# Connecteurs.net
KiCad netlist of a schematic drawn in Altium Designer
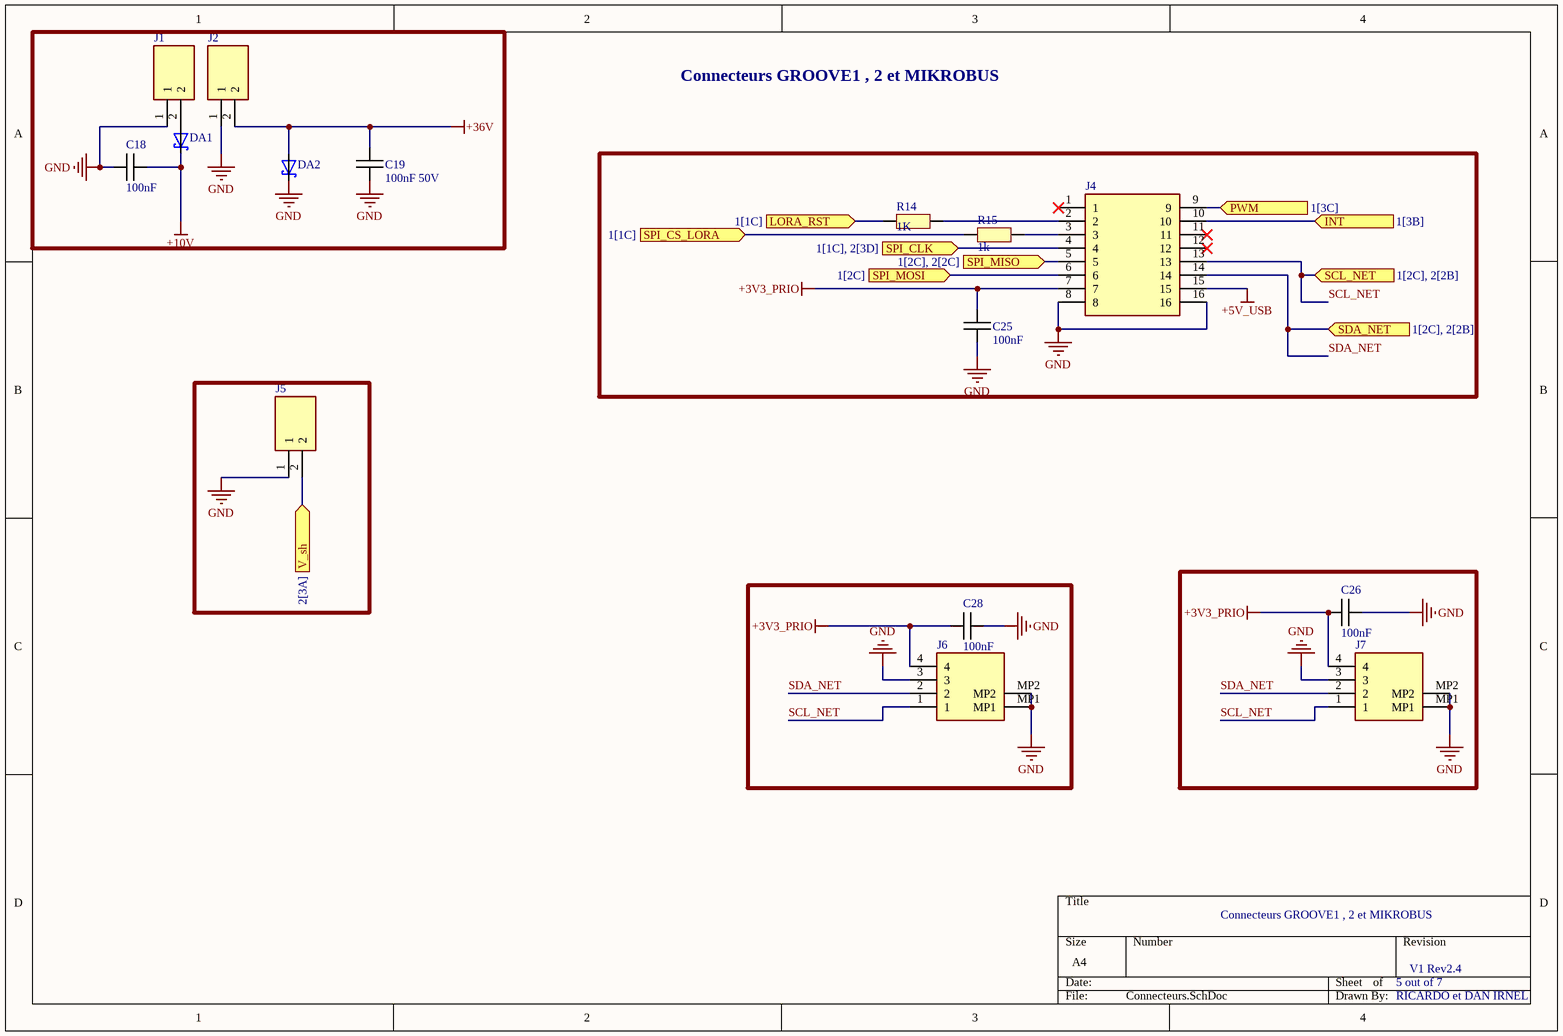
[diagram p0: Connecteurs.SchDoc]

(export (version "E")
  (design (tool "Eeschema 10.0.6"))
  (components
    (comp (ref "C18")
      (value "100nF")
      (footprint "CAPC1005X06N")
      (libsource (lib "SCHLibrary") (part "Capacitor"))
    )
    (comp (ref "C19")
      (value "100nF 50V")
      (footprint "CAPC1005X06N")
      (libsource (lib "SCHLibrary") (part "Capacitor"))
    )
    (comp (ref "C25")
      (value "100nF")
      (footprint "CAPC1005X06N")
      (libsource (lib "SCHLibrary") (part "Capacitor"))
    )
    (comp (ref "C26")
      (value "100nF")
      (footprint "CAPC1005X06N")
      (libsource (lib "SCHLibrary") (part "Capacitor"))
    )
    (comp (ref "C28")
      (value "100nF")
      (footprint "CAPC1005X06N")
      (libsource (lib "SCHLibrary") (part "Capacitor"))
    )
    (comp (ref "DA1")
      (value "SD103AWS-7-F")
      (footprint "SD103AWS-7-F")
      (description "Diode Array 3 Independent Schottky 40V 175mA Surface Mount 6-TSSOP, SC-88, SOT-363")
      (libsource (lib "SCHLibrary") (part "SD103AWS-7-F"))
    )
    (comp (ref "DA2")
      (value "SD103AWS-7-F")
      (footprint "SD103AWS-7-F")
      (description "Diode Array 3 Independent Schottky 40V 175mA Surface Mount 6-TSSOP, SC-88, SOT-363")
      (libsource (lib "SCHLibrary") (part "SD103AWS-7-F"))
    )
    (comp (ref "J1")
      (value "61300211121")
      (footprint "61300211121")
      (description "WURTH ELEKTRONIK - 61300211121 - HEADER, 2.54MM, PIN, THT, VERTICAL, 2WAY")
      (libsource (lib "SCHLibrary") (part "61300211121"))
    )
    (comp (ref "J2")
      (value "61300211121")
      (footprint "61300211121")
      (description "WURTH ELEKTRONIK - 61300211121 - HEADER, 2.54MM, PIN, THT, VERTICAL, 2WAY")
      (libsource (lib "SCHLibrary") (part "61300211121"))
    )
    (comp (ref "J4")
      (value "825433-8")
      (footprint "Connect-Mikrobus")
      (description "Headers & Wire Housings 8P double for connection mikrobus")
      (fields (field (name "MOUSER PART NUMBER") "571-825433-8"))
      (libsource (lib "SCHLibrary") (part "Connect-Mikrobus"))
    )
    (comp (ref "J5")
      (value "61300211121")
      (footprint "61300211121")
      (description "WURTH ELEKTRONIK - 61300211121 - HEADER, 2.54MM, PIN, THT, VERTICAL, 2WAY")
      (libsource (lib "SCHLibrary") (part "61300211121"))
    )
    (comp (ref "J6")
      (value "114020164")
      (footprint "114020164")
      (description "Seeed Studio Accessories Grove Female Header - SMD-4P-2.0mm-90D-20Pcs")
      (fields (field (name "MOUSER PART NUMBER") "713-114020164"))
      (libsource (lib "SCHLibrary") (part "114020164"))
    )
    (comp (ref "J7")
      (value "114020164")
      (footprint "114020164")
      (description "Seeed Studio Accessories Grove Female Header - SMD-4P-2.0mm-90D-20Pcs")
      (fields (field (name "MOUSER PART NUMBER") "713-114020164"))
      (libsource (lib "SCHLibrary") (part "114020164"))
    )
    (comp (ref "R14")
      (value "1K")
      (footprint "RESC1005X06N")
      (libsource (lib "SCHLibrary") (part "Resistor"))
    )
    (comp (ref "R15")
      (value "1k")
      (footprint "RESC1005X06N")
      (libsource (lib "SCHLibrary") (part "Resistor"))
    )
  )
  (nets
    (net (code "1") (name "+3V3_PRIO") (class "Default")
      (node (ref "C25") (pin "1") (pinfunction "1_1") (pintype "passive"))
      (node (ref "C26") (pin "2") (pinfunction "2_2") (pintype "passive"))
      (node (ref "C28") (pin "2") (pinfunction "2_2") (pintype "passive"))
      (node (ref "J4") (pin "7") (pinfunction "7_7") (pintype "passive"))
      (node (ref "J6") (pin "4") (pinfunction "4_4") (pintype "passive"))
      (node (ref "J7") (pin "4") (pinfunction "4_4") (pintype "passive"))
    )
    (net (code "2") (name "+5V_USB") (class "Default")
      (node (ref "J4") (pin "15") (pinfunction "15_15") (pintype "passive"))
    )
    (net (code "3") (name "+10V") (class "Default")
      (node (ref "C18") (pin "1") (pinfunction "1_1") (pintype "passive"))
      (node (ref "DA1") (pin "1") (pinfunction "C_1") (pintype "passive"))
    )
    (net (code "4") (name "+36V") (class "Default")
      (node (ref "C19") (pin "1") (pinfunction "1_1") (pintype "passive"))
      (node (ref "DA2") (pin "2") (pinfunction "A_2") (pintype "passive"))
      (node (ref "J2") (pin "2") (pinfunction "2_2") (pintype "passive"))
    )
    (net (code "5") (name "/INT") (class "Default")
      (node (ref "J4") (pin "10") (pinfunction "10_10") (pintype "passive"))
    )
    (net (code "6") (name "/LORA_RST") (class "Default")
      (node (ref "R14") (pin "1") (pinfunction "1_1") (pintype "passive"))
    )
    (net (code "7") (name "/PWM") (class "Default")
      (node (ref "J4") (pin "9") (pinfunction "9_9") (pintype "passive"))
    )
    (net (code "8") (name "/SCL_NET") (class "Default")
      (node (ref "J4") (pin "13") (pinfunction "13_13") (pintype "passive"))
      (node (ref "J6") (pin "1") (pinfunction "1_1") (pintype "passive"))
      (node (ref "J7") (pin "1") (pinfunction "1_1") (pintype "passive"))
    )
    (net (code "9") (name "/SDA_NET") (class "Default")
      (node (ref "J4") (pin "14") (pinfunction "14_14") (pintype "passive"))
      (node (ref "J6") (pin "2") (pinfunction "2_2") (pintype "passive"))
      (node (ref "J7") (pin "2") (pinfunction "2_2") (pintype "passive"))
    )
    (net (code "10") (name "/SPI_CLK") (class "Default")
      (node (ref "J4") (pin "4") (pinfunction "4_4") (pintype "passive"))
    )
    (net (code "11") (name "/SPI_CS_LORA") (class "Default")
      (node (ref "R15") (pin "1") (pinfunction "1_1") (pintype "passive"))
    )
    (net (code "12") (name "/SPI_MISO") (class "Default")
      (node (ref "J4") (pin "5") (pinfunction "5_5") (pintype "passive"))
    )
    (net (code "13") (name "/SPI_MOSI") (class "Default")
      (node (ref "J4") (pin "6") (pinfunction "6_6") (pintype "passive"))
    )
    (net (code "14") (name "/V_sh") (class "Default")
      (node (ref "J5") (pin "2") (pinfunction "2_2") (pintype "passive"))
    )
    (net (code "15") (name "GND") (class "Default")
      (node (ref "C18") (pin "2") (pinfunction "2_2") (pintype "passive"))
      (node (ref "C19") (pin "2") (pinfunction "2_2") (pintype "passive"))
      (node (ref "C25") (pin "2") (pinfunction "2_2") (pintype "passive"))
      (node (ref "C26") (pin "1") (pinfunction "1_1") (pintype "passive"))
      (node (ref "C28") (pin "1") (pinfunction "1_1") (pintype "passive"))
      (node (ref "DA2") (pin "1") (pinfunction "C_1") (pintype "passive"))
      (node (ref "J1") (pin "1") (pinfunction "1_1") (pintype "passive"))
      (node (ref "J2") (pin "1") (pinfunction "1_1") (pintype "passive"))
      (node (ref "J4") (pin "16") (pinfunction "16_16") (pintype "passive"))
      (node (ref "J4") (pin "8") (pinfunction "8_8") (pintype "passive"))
      (node (ref "J5") (pin "1") (pinfunction "1_1") (pintype "passive"))
      (node (ref "J6") (pin "3") (pinfunction "3_3") (pintype "passive"))
      (node (ref "J6") (pin "MP1") (pinfunction "MP1_MP1") (pintype "passive"))
      (node (ref "J6") (pin "MP2") (pinfunction "MP2_MP2") (pintype "passive"))
      (node (ref "J7") (pin "3") (pinfunction "3_3") (pintype "passive"))
      (node (ref "J7") (pin "MP1") (pinfunction "MP1_MP1") (pintype "passive"))
      (node (ref "J7") (pin "MP2") (pinfunction "MP2_MP2") (pintype "passive"))
    )
    (net (code "16") (name "Net-(DA1-A)") (class "Default")
      (node (ref "DA1") (pin "2") (pinfunction "A_2") (pintype "passive"))
      (node (ref "J1") (pin "2") (pinfunction "2_2") (pintype "passive"))
    )
    (net (code "17") (name "Net-(J4-Pad2)") (class "Default")
      (node (ref "J4") (pin "2") (pinfunction "2_2") (pintype "passive"))
      (node (ref "R14") (pin "2") (pinfunction "2_2") (pintype "passive"))
    )
    (net (code "18") (name "Net-(J4-Pad3)") (class "Default")
      (node (ref "J4") (pin "3") (pinfunction "3_3") (pintype "passive"))
      (node (ref "R15") (pin "2") (pinfunction "2_2") (pintype "passive"))
    )
    (net (code "19") (name "unconnected-(J4-Pad1)") (class "Default")
      (node (ref "J4") (pin "1") (pinfunction "1_1") (pintype "passive+no_connect"))
    )
    (net (code "20") (name "unconnected-(J4-Pad11)") (class "Default")
      (node (ref "J4") (pin "11") (pinfunction "11_11") (pintype "passive+no_connect"))
    )
    (net (code "21") (name "unconnected-(J4-Pad12)") (class "Default")
      (node (ref "J4") (pin "12") (pinfunction "12_12") (pintype "passive+no_connect"))
    )
  )
)
